# Fan_Controller.net
KiCad netlist of a schematic drawn in Altium Designer
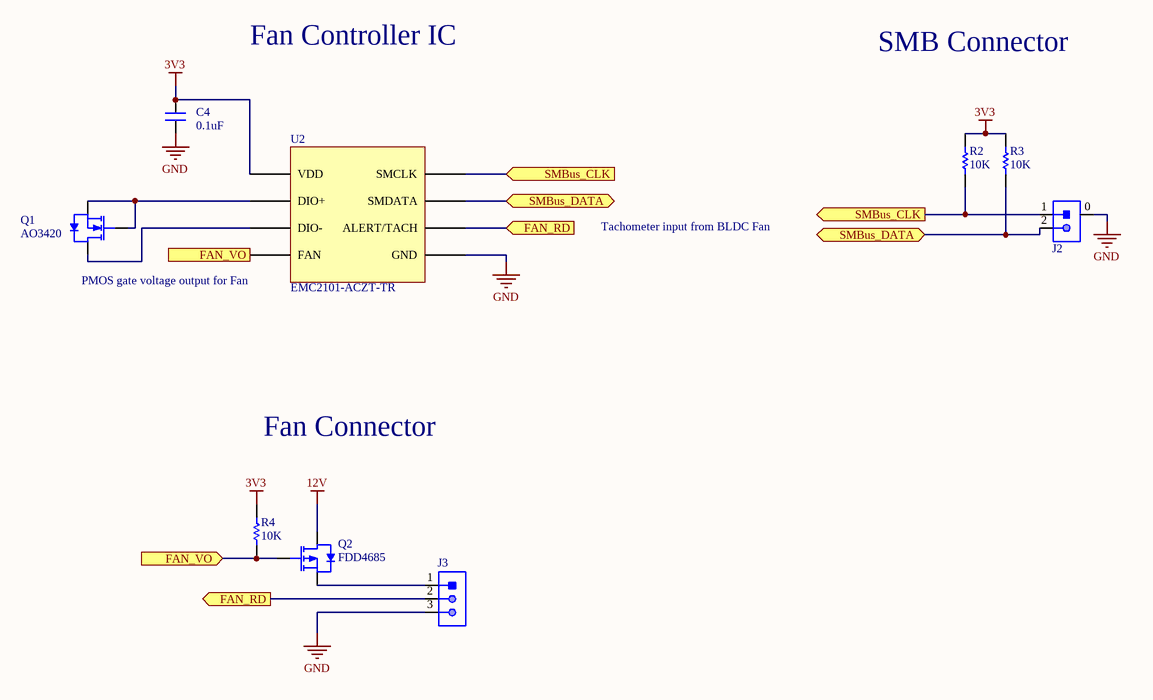
[diagram p0: Fan Controller.SchDoc]

(export (version "E")
  (design (tool "Eeschema 10.0.6"))
  (components
    (comp (ref "C4")
      (value "0.1uF")
      (footprint "CAPC2012X140N")
      (description "CAP CER 0.1UF 50V X7R 0805")
      (fields (field (name "TOLERANCE") "10%") (field (name "Comment") "CAP_0.1uF_50V_0805"))
      (libsource (lib "UWRT_Schematic_Library_2020") (part "CAP_0.1uF_50V_0805"))
    )
    (comp (ref "J2")
      (value "CON_2M_SM4")
      (footprint "JST-B2B-SM4-TB")
      (description "CONN HEADER SMD 2POS 2MM")
      (libsource (lib "UWRT_Schematic_Library_2020") (part "CON_2M_SM4"))
    )
    (comp (ref "J3")
      (value "CON_3M_TERM")
      (footprint "3 PIN TERM")
      (description "TERM BLK 3POS SIDE ENTRY 5MM PCB")
      (libsource (lib "UWRT_Schematic_Library_2020") (part "CON_3M_TERM"))
    )
    (comp (ref "Q1")
      (value "NMOS_20V_6A")
      (footprint "NMOS_SOT23-3")
      (description "MOSFET N-CH 20V 6A SOT23")
      (fields (field (name "MANUFACTURER PART NUMBER 1") "AO3420"))
      (libsource (lib "UWRT_Schematic_Library_2020") (part "NMOS_20V_6A"))
    )
    (comp (ref "Q2")
      (value "PMOS_40V_8.4A")
      (footprint "D-PAK")
      (description "MOSFET P-CH 40V 8.4A D-PAK")
      (fields (field (name "MANUFACTURER PART NUMBER 1") "FDD4685"))
      (libsource (lib "UWRT_Schematic_Library_2020") (part "PMOS_40V_8.4A"))
    )
    (comp (ref "R2")
      (value "10K")
      (footprint "RESC0603(1608)_N")
      (description "RES SMD 10K OHM 5% 1/10W 0603")
      (fields (field (name "TOLERANCE") "5%") (field (name "Comment") "RES_10K_0603"))
      (libsource (lib "UWRT_Schematic_Library_2020") (part "RES_10K_0603"))
    )
    (comp (ref "R3")
      (value "10K")
      (footprint "RESC0603(1608)_N")
      (description "RES SMD 10K OHM 5% 1/10W 0603")
      (fields (field (name "TOLERANCE") "5%") (field (name "Comment") "RES_10K_0603"))
      (libsource (lib "UWRT_Schematic_Library_2020") (part "RES_10K_0603"))
    )
    (comp (ref "R4")
      (value "10K")
      (footprint "RESC0603(1608)_N")
      (description "RES SMD 10K OHM 5% 1/10W 0603")
      (fields (field (name "TOLERANCE") "5%") (field (name "Comment") "RES_10K_0603"))
      (libsource (lib "UWRT_Schematic_Library_2020") (part "RES_10K_0603"))
    )
    (comp (ref "U2")
      (value "EMC2101-ACZT-TR")
      (footprint "SOIC-8_SG")
      (description "SMBUS FAN CONTROL WITH TEMP MONITORING")
      (libsource (lib "UWRT_Schematic_Library_2020") (part "EMC2101-ACZT-TR"))
    )
  )
  (nets
    (net (code "1") (name "/FAN_RD") (class "Default")
      (node (ref "J3") (pin "2") (pinfunction "2_2") (pintype "passive"))
      (node (ref "U2") (pin "6") (pinfunction "ALERT/TACH_6") (pintype "passive"))
    )
    (net (code "2") (name "/FAN_VO") (class "Default")
      (node (ref "Q2") (pin "2") (pinfunction "Gate_2") (pintype "passive"))
      (node (ref "R4") (pin "2") (pinfunction "2_2") (pintype "passive"))
      (node (ref "U2") (pin "4") (pinfunction "FAN_4") (pintype "passive"))
    )
    (net (code "3") (name "/SMBus_CLK") (class "Default")
      (node (ref "J2") (pin "1") (pinfunction "1_1") (pintype "passive"))
      (node (ref "R2") (pin "1") (pinfunction "1_1") (pintype "passive"))
      (node (ref "U2") (pin "8") (pinfunction "SMCLK_8") (pintype "passive"))
    )
    (net (code "4") (name "/SMBus_DATA") (class "Default")
      (node (ref "J2") (pin "2") (pinfunction "2_2") (pintype "passive"))
      (node (ref "R3") (pin "1") (pinfunction "1_1") (pintype "passive"))
      (node (ref "U2") (pin "7") (pinfunction "SMDATA_7") (pintype "passive"))
    )
    (net (code "5") (name "3V3") (class "Default")
      (node (ref "C4") (pin "2") (pinfunction "2_2") (pintype "passive"))
      (node (ref "R2") (pin "2") (pinfunction "2_2") (pintype "passive"))
      (node (ref "R3") (pin "2") (pinfunction "2_2") (pintype "passive"))
      (node (ref "R4") (pin "1") (pinfunction "1_1") (pintype "passive"))
      (node (ref "U2") (pin "1") (pinfunction "VDD_1") (pintype "passive"))
    )
    (net (code "6") (name "12V") (class "Default")
      (node (ref "Q2") (pin "1") (pinfunction "Drain_1") (pintype "passive"))
    )
    (net (code "7") (name "GND") (class "Default")
      (node (ref "C4") (pin "1") (pinfunction "1_1") (pintype "passive"))
      (node (ref "J2") (pin "0") (pinfunction "0_0") (pintype "passive"))
      (node (ref "J3") (pin "3") (pinfunction "3_3") (pintype "passive"))
      (node (ref "U2") (pin "5") (pinfunction "GND_5") (pintype "passive"))
    )
    (net (code "8") (name "Net-(Q1-D)") (class "Default")
      (node (ref "Q1") (pin "3") (pinfunction "D_3") (pintype "passive"))
      (node (ref "U2") (pin "3") (pinfunction "DIO-_3") (pintype "passive"))
    )
    (net (code "9") (name "Net-(Q1-G)") (class "Default")
      (node (ref "Q1") (pin "1") (pinfunction "G_1") (pintype "passive"))
      (node (ref "Q1") (pin "2") (pinfunction "S_2") (pintype "passive"))
      (node (ref "U2") (pin "2") (pinfunction "DIO+_2") (pintype "passive"))
    )
    (net (code "10") (name "Net-(Q2-Source)") (class "Default")
      (node (ref "J3") (pin "1") (pinfunction "1_1") (pintype "passive"))
      (node (ref "Q2") (pin "3") (pinfunction "Source_3") (pintype "passive"))
    )
  )
)
